# PCBdesign.net
KiCad netlist of a schematic drawn in Altium Designer
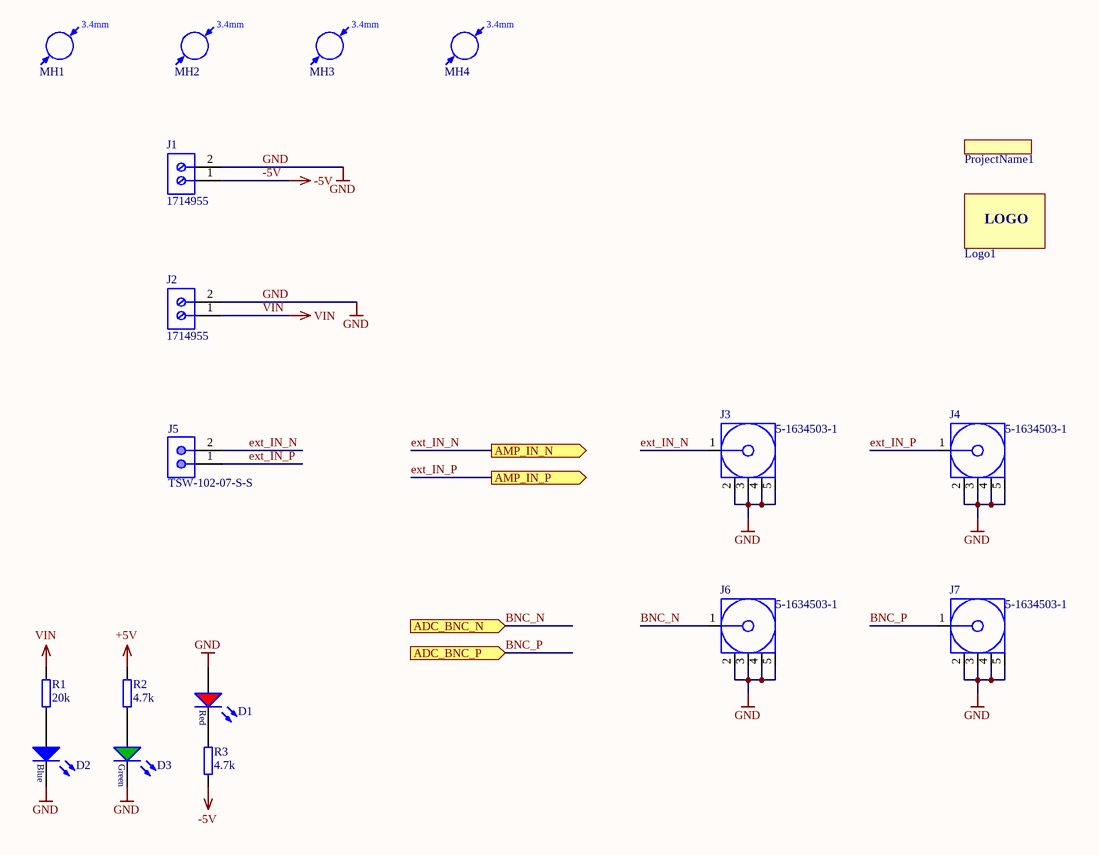
[diagram p0: PCBdesign.SchDoc]

(export (version "E")
  (design (tool "Eeschema 10.0.6"))
  (components
    (comp (ref "D1")
      (value "150060RS75000")
      (footprint "WL-SMCW_0603")
      (description "WL-SMCW SMD Mono-color Chip LED Waterclear, size 0603, Red, 2 V, 140°")
      (fields (field (name "MF") "Wuerth Elektronik") (field (name "CREATED") "2018_09_06_AGeiger"))
      (libsource (lib "neg5V") (part "LED_Red_0603"))
    )
    (comp (ref "D2")
      (value "150060BS75000")
      (footprint "WL-SMCW_0603")
      (description "WL-SMCW SMD Mono-color Chip LED Waterclear, size 0603, Blue, 3.2 V, 140°")
      (fields (field (name "MF") "Wuerth Elektronik") (field (name "CREATED") "2018_09_06_AGeiger"))
      (libsource (lib "neg5V") (part "LED_Blue_0603"))
    )
    (comp (ref "D3")
      (value "150060GS75000")
      (footprint "WL-SMCW_0603")
      (description "WL-SMCW SMD Mono-color Chip LED Waterclear, size 0603, Green, 3.2 V, 140°")
      (fields (field (name "MF") "Wuerth Elektronik") (field (name "CREATED") "2018_09_06_AGeiger"))
      (libsource (lib "neg5V") (part "LED_Green_0603"))
    )
    (comp (ref "J1")
      (value "1714955")
      (footprint "PHOE-1714955_V")
      (description "Conn Terminal Blocks 2 POS 6.35mm Solder ST Thru-Hole 32A")
      (fields (field (name "MANUFACTURER") "Phoenix Contact") (field (name "VOLTAGE") "300V"))
      (libsource (lib "neg5V") (part "1714955"))
    )
    (comp (ref "J2")
      (value "1714955")
      (footprint "PHOE-1714955_V")
      (description "Conn Terminal Blocks 2 POS 6.35mm Solder ST Thru-Hole 32A")
      (fields (field (name "MANUFACTURER") "Phoenix Contact") (field (name "VOLTAGE") "300V"))
      (libsource (lib "neg5V") (part "1714955"))
    )
    (comp (ref "J3")
      (value "5-1634503-1")
      (footprint "TECO-5-1634503-1_V")
      (description "BNC Str PCB Skt 50Ohm Nickel Pltd")
      (fields (field (name "MANUFACTURER") "TE Connectivity"))
      (libsource (lib "neg5V") (part "5-1634503-1"))
    )
    (comp (ref "J4")
      (value "5-1634503-1")
      (footprint "TECO-5-1634503-1_V")
      (description "BNC Str PCB Skt 50Ohm Nickel Pltd")
      (fields (field (name "MANUFACTURER") "TE Connectivity"))
      (libsource (lib "neg5V") (part "5-1634503-1"))
    )
    (comp (ref "J5")
      (value "TSW-102-07-S-S")
      (footprint "SMTC-TSW-102-07-S-S")
      (description "SAMTEC         TSW-102-07-S-S             CONNECTOR, HEADER, 2 POSITION, 1ROW, 2.54MM")
      (fields (field (name "MANUFACTURER") "Samtec"))
      (libsource (lib "neg5V") (part "TSW-102-07-S-S"))
    )
    (comp (ref "J6")
      (value "5-1634503-1")
      (footprint "TECO-5-1634503-1_V")
      (description "BNC Str PCB Skt 50Ohm Nickel Pltd")
      (fields (field (name "MANUFACTURER") "TE Connectivity"))
      (libsource (lib "neg5V") (part "5-1634503-1"))
    )
    (comp (ref "J7")
      (value "5-1634503-1")
      (footprint "TECO-5-1634503-1_V")
      (description "BNC Str PCB Skt 50Ohm Nickel Pltd")
      (fields (field (name "MANUFACTURER") "TE Connectivity"))
      (libsource (lib "neg5V") (part "5-1634503-1"))
    )
    (comp (ref "Logo1") (value "~") (footprint "LOGO_Tum") (libsource (lib "neg5V") (part "Logos")))
    (comp (ref "MH1")
      (value "mounting hole 3,4mm")
      (footprint "MH_3.4")
      (description "Non plated through hole, 3.4mm")
      (libsource (lib "neg5V") (part "Mounting Hole"))
    )
    (comp (ref "MH2")
      (value "mounting hole 3,4mm")
      (footprint "MH_3.4")
      (description "Non plated through hole, 3.4mm")
      (libsource (lib "neg5V") (part "Mounting Hole"))
    )
    (comp (ref "MH3")
      (value "mounting hole 3,4mm")
      (footprint "MH_3.4")
      (description "Non plated through hole, 3.4mm")
      (libsource (lib "neg5V") (part "Mounting Hole"))
    )
    (comp (ref "MH4")
      (value "mounting hole 3,4mm")
      (footprint "MH_3.4")
      (description "Non plated through hole, 3.4mm")
      (libsource (lib "neg5V") (part "Mounting Hole"))
    )
    (comp (ref "ProjectName1")
      (value "Project Name, Rev")
      (footprint "ID_ProjectRev")
      (description "Project Name and Revision Number")
      (fields (field (name "CREATED") "2018_11_23_AGeiger"))
      (libsource (lib "neg5V") (part "ID_ProjectRev"))
    )
    (comp (ref "R1")
      (value "20k")
      (footprint "RESC1608X06N")
      (fields (field (name "MF") "CRCW060320K0JNEAC") (field (name "MPN") "Vishay / Dale"))
      (libsource (lib "neg5V") (part "R_0603"))
    )
    (comp (ref "R2")
      (value "4.7k")
      (footprint "RESC1608X06N")
      (fields (field (name "MF") "Vishay / Dale") (field (name "MPN") "CRCW06034K70JNEAC"))
      (libsource (lib "neg5V") (part "R_0603"))
    )
    (comp (ref "R3")
      (value "4.7k")
      (footprint "RESC1608X06N")
      (fields (field (name "MF") "Vishay / Dale") (field (name "MPN") "CRCW06034K70JNEAC"))
      (libsource (lib "neg5V") (part "R_0603"))
    )
  )
  (nets
    (net (code "1") (name "+5V") (class "Default") (node (ref "R2") (pin "2") (pintype "passive")))
    (net (code "2") (name "-5V") (class "Default")
      (node (ref "J1") (pin "1") (pinfunction "1_1") (pintype "passive"))
      (node (ref "R3") (pin "1") (pintype "passive"))
    )
    (net (code "3") (name "/BNC_N") (class "Default")
      (node (ref "J6") (pin "1") (pinfunction "1_1") (pintype "passive"))
    )
    (net (code "4") (name "/BNC_P") (class "Default")
      (node (ref "J7") (pin "1") (pinfunction "1_1") (pintype "passive"))
    )
    (net (code "5") (name "/ext_IN_N") (class "Default")
      (node (ref "J3") (pin "1") (pinfunction "1_1") (pintype "passive"))
      (node (ref "J5") (pin "2") (pinfunction "2_2") (pintype "passive"))
    )
    (net (code "6") (name "/ext_IN_P") (class "Default")
      (node (ref "J4") (pin "1") (pinfunction "1_1") (pintype "passive"))
      (node (ref "J5") (pin "1") (pinfunction "1_1") (pintype "passive"))
    )
    (net (code "7") (name "GND") (class "Default")
      (node (ref "D1") (pin "2") (pinfunction "A_2") (pintype "passive"))
      (node (ref "D2") (pin "1") (pinfunction "K_1") (pintype "passive"))
      (node (ref "D3") (pin "1") (pinfunction "K_1") (pintype "passive"))
      (node (ref "J1") (pin "2") (pinfunction "2_2") (pintype "passive"))
      (node (ref "J2") (pin "2") (pinfunction "2_2") (pintype "passive"))
      (node (ref "J3") (pin "2") (pinfunction "2_2") (pintype "passive"))
      (node (ref "J3") (pin "3") (pinfunction "3_3") (pintype "passive"))
      (node (ref "J3") (pin "4") (pinfunction "4_4") (pintype "passive"))
      (node (ref "J3") (pin "5") (pinfunction "5_5") (pintype "passive"))
      (node (ref "J4") (pin "2") (pinfunction "2_2") (pintype "passive"))
      (node (ref "J4") (pin "3") (pinfunction "3_3") (pintype "passive"))
      (node (ref "J4") (pin "4") (pinfunction "4_4") (pintype "passive"))
      (node (ref "J4") (pin "5") (pinfunction "5_5") (pintype "passive"))
      (node (ref "J6") (pin "2") (pinfunction "2_2") (pintype "passive"))
      (node (ref "J6") (pin "3") (pinfunction "3_3") (pintype "passive"))
      (node (ref "J6") (pin "4") (pinfunction "4_4") (pintype "passive"))
      (node (ref "J6") (pin "5") (pinfunction "5_5") (pintype "passive"))
      (node (ref "J7") (pin "2") (pinfunction "2_2") (pintype "passive"))
      (node (ref "J7") (pin "3") (pinfunction "3_3") (pintype "passive"))
      (node (ref "J7") (pin "4") (pinfunction "4_4") (pintype "passive"))
      (node (ref "J7") (pin "5") (pinfunction "5_5") (pintype "passive"))
    )
    (net (code "8") (name "Net-(D1-K)") (class "Default")
      (node (ref "D1") (pin "1") (pinfunction "K_1") (pintype "passive"))
      (node (ref "R3") (pin "2") (pintype "passive"))
    )
    (net (code "9") (name "Net-(D2-A)") (class "Default")
      (node (ref "D2") (pin "2") (pinfunction "A_2") (pintype "passive"))
      (node (ref "R1") (pin "1") (pintype "passive"))
    )
    (net (code "10") (name "Net-(D3-A)") (class "Default")
      (node (ref "D3") (pin "2") (pinfunction "A_2") (pintype "passive"))
      (node (ref "R2") (pin "1") (pintype "passive"))
    )
    (net (code "11") (name "VIN") (class "Default")
      (node (ref "J2") (pin "1") (pinfunction "1_1") (pintype "passive"))
      (node (ref "R1") (pin "2") (pintype "passive"))
    )
  )
)
